# 1_-_MCU-CORE.net
KiCad netlist of a schematic drawn in Altium Designer
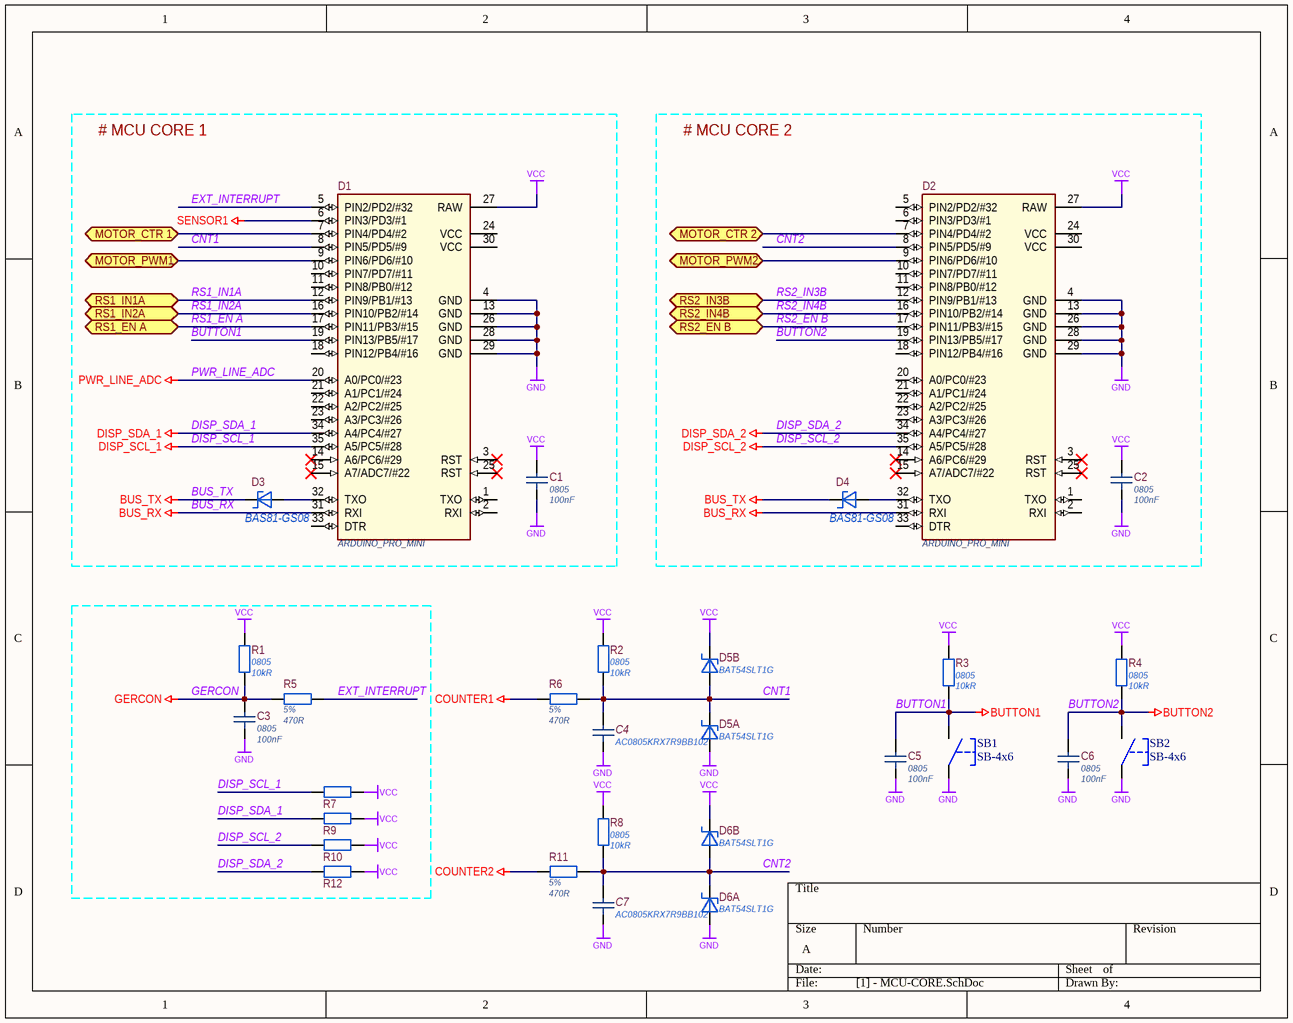
[diagram p0: [1] - MCU-CORE.SchDoc]

(export (version "E")
  (design (tool "Eeschema 10.0.6"))
  (components
    (comp (ref "C1")
      (value "AC0805KRX7R9BB104")
      (footprint "CH0805C")
      (description "0.10µF 50V Ceramic Capacitor X7R 0805 (2012 Metric) 0.079\" L x 0.049\" W (2.00mm x 1.25mm)")
      (fields
        (field (name "CASE/PACKAGE") "0805")
        (field (name "CAPACITANCE") "100nF")
        (field (name "TOLERANCE") "10%")
      )
      (libsource (lib "Chip Capacitors") (part "AC0805KRX7R9BB104"))
    )
    (comp (ref "C2")
      (value "AC0805KRX7R9BB104")
      (footprint "CH0805C")
      (description "0.10µF 50V Ceramic Capacitor X7R 0805 (2012 Metric) 0.079\" L x 0.049\" W (2.00mm x 1.25mm)")
      (fields
        (field (name "CASE/PACKAGE") "0805")
        (field (name "CAPACITANCE") "100nF")
        (field (name "TOLERANCE") "10%")
      )
      (libsource (lib "Chip Capacitors") (part "AC0805KRX7R9BB104"))
    )
    (comp (ref "C3")
      (value "AC0805KRX7R9BB104")
      (footprint "CH0805C")
      (description "0.10µF 50V Ceramic Capacitor X7R 0805 (2012 Metric) 0.079\" L x 0.049\" W (2.00mm x 1.25mm)")
      (fields
        (field (name "CASE/PACKAGE") "0805")
        (field (name "CAPACITANCE") "100nF")
        (field (name "TOLERANCE") "10%")
      )
      (libsource (lib "Chip Capacitors") (part "AC0805KRX7R9BB104"))
    )
    (comp (ref "C4")
      (value "AC0805KRX7R9BB102")
      (footprint "CH0805C")
      (description "CAP CER 1000PF 50V X7R 0805")
      (libsource (lib "Chip Capacitors") (part "AC0805KRX7R9BB102"))
    )
    (comp (ref "C5")
      (value "AC0805KRX7R9BB104")
      (footprint "CH0805C")
      (description "0.10µF 50V Ceramic Capacitor X7R 0805 (2012 Metric) 0.079\" L x 0.049\" W (2.00mm x 1.25mm)")
      (fields
        (field (name "CASE/PACKAGE") "0805")
        (field (name "CAPACITANCE") "100nF")
        (field (name "TOLERANCE") "10%")
      )
      (libsource (lib "Chip Capacitors") (part "AC0805KRX7R9BB104"))
    )
    (comp (ref "C6")
      (value "AC0805KRX7R9BB104")
      (footprint "CH0805C")
      (description "0.10µF 50V Ceramic Capacitor X7R 0805 (2012 Metric) 0.079\" L x 0.049\" W (2.00mm x 1.25mm)")
      (fields
        (field (name "CASE/PACKAGE") "0805")
        (field (name "CAPACITANCE") "100nF")
        (field (name "TOLERANCE") "10%")
      )
      (libsource (lib "Chip Capacitors") (part "AC0805KRX7R9BB104"))
    )
    (comp (ref "C7")
      (value "AC0805KRX7R9BB102")
      (footprint "CH0805C")
      (description "CAP CER 1000PF 50V X7R 0805")
      (libsource (lib "Chip Capacitors") (part "AC0805KRX7R9BB102"))
    )
    (comp (ref "D1")
      (value "ARDUINO_PRO_MINI")
      (footprint "DEV-11114")
      (description "ATMEGA328 ARDUINO PRO MINI 3.3V")
      (libsource (lib "Modules") (part "ARDUINO_PRO_MINI"))
    )
    (comp (ref "D2")
      (value "ARDUINO_PRO_MINI")
      (footprint "DEV-11114")
      (description "ATMEGA328 ARDUINO PRO MINI 3.3V")
      (libsource (lib "Modules") (part "ARDUINO_PRO_MINI"))
    )
    (comp (ref "D3")
      (value "BAS81-GS08")
      (footprint "SOD-80")
      (description "Diode Small Signal Schottky 40V 0.03A 2-Pin Mini-MELF SOD-80 T/R")
      (libsource (lib "Diodes") (part "BAS81-GS08"))
    )
    (comp (ref "D4")
      (value "BAS81-GS08")
      (footprint "SOD-80")
      (description "Diode Small Signal Schottky 40V 0.03A 2-Pin Mini-MELF SOD-80 T/R")
      (libsource (lib "Diodes") (part "BAS81-GS08"))
    )
    (comp (ref "D5")
      (value "BAT54SLT1G")
      (footprint "SOT23-3")
      (description "DIODE ARRAY SCHOTTKY 30V SOT23-3")
      (libsource (lib "Diodes") (part "BAT54SLT1G"))
    )
    (comp (ref "D6")
      (value "BAT54SLT1G")
      (footprint "SOT23-3")
      (description "DIODE ARRAY SCHOTTKY 30V SOT23-3")
      (libsource (lib "Diodes") (part "BAT54SLT1G"))
    )
    (comp (ref "R1")
      (value "RC0805JR-0710KL")
      (footprint "CH0805R")
      (description "RES SMD 10K OHM 5% 1/8W 0805")
      (fields
        (field (name "CASE/PACKAGE") "0805")
        (field (name "TOLERANCE") "5%")
        (field (name "RESISTANCE") "10kR")
      )
      (libsource (lib "Chip Resistors") (part "RC0805JR-0710KL"))
    )
    (comp (ref "R2")
      (value "RC0805JR-0710KL")
      (footprint "CH0805R")
      (description "RES SMD 10K OHM 5% 1/8W 0805")
      (fields
        (field (name "CASE/PACKAGE") "0805")
        (field (name "TOLERANCE") "5%")
        (field (name "RESISTANCE") "10kR")
      )
      (libsource (lib "Chip Resistors") (part "RC0805JR-0710KL"))
    )
    (comp (ref "R3")
      (value "RC0805JR-0710KL")
      (footprint "CH0805R")
      (description "RES SMD 10K OHM 5% 1/8W 0805")
      (fields
        (field (name "CASE/PACKAGE") "0805")
        (field (name "TOLERANCE") "5%")
        (field (name "RESISTANCE") "10kR")
      )
      (libsource (lib "Chip Resistors") (part "RC0805JR-0710KL"))
    )
    (comp (ref "R4")
      (value "RC0805JR-0710KL")
      (footprint "CH0805R")
      (description "RES SMD 10K OHM 5% 1/8W 0805")
      (fields
        (field (name "CASE/PACKAGE") "0805")
        (field (name "TOLERANCE") "5%")
        (field (name "RESISTANCE") "10kR")
      )
      (libsource (lib "Chip Resistors") (part "RC0805JR-0710KL"))
    )
    (comp (ref "R5")
      (value "RC0805JR-07470RL")
      (footprint "CH0805R")
      (description "RES SMD 470 OHM 5% 1/8W 0805")
      (fields (field (name "TOLERANCE") "5%") (field (name "RESISTANCE") "470R"))
      (libsource (lib "Chip Resistors") (part "RC0805JR-07470RL"))
    )
    (comp (ref "R6")
      (value "RC0805JR-07470RL")
      (footprint "CH0805R")
      (description "RES SMD 470 OHM 5% 1/8W 0805")
      (fields (field (name "TOLERANCE") "5%") (field (name "RESISTANCE") "470R"))
      (libsource (lib "Chip Resistors") (part "RC0805JR-07470RL"))
    )
    (comp (ref "R7")
      (value "RC0805JR-074K7L")
      (footprint "CH0805R")
      (description "RES SMD 4.7K OHM 5% 1/8W 0805")
      (fields (field (name "TOLERANCE") "5%"))
      (libsource (lib "Chip Resistors") (part "RC0805JR-074K7L"))
    )
    (comp (ref "R8")
      (value "RC0805JR-0710KL")
      (footprint "CH0805R")
      (description "RES SMD 10K OHM 5% 1/8W 0805")
      (fields
        (field (name "CASE/PACKAGE") "0805")
        (field (name "TOLERANCE") "5%")
        (field (name "RESISTANCE") "10kR")
      )
      (libsource (lib "Chip Resistors") (part "RC0805JR-0710KL"))
    )
    (comp (ref "R9")
      (value "RC0805JR-074K7L")
      (footprint "CH0805R")
      (description "RES SMD 4.7K OHM 5% 1/8W 0805")
      (fields (field (name "TOLERANCE") "5%"))
      (libsource (lib "Chip Resistors") (part "RC0805JR-074K7L"))
    )
    (comp (ref "R10")
      (value "RC0805JR-074K7L")
      (footprint "CH0805R")
      (description "RES SMD 4.7K OHM 5% 1/8W 0805")
      (fields (field (name "TOLERANCE") "5%"))
      (libsource (lib "Chip Resistors") (part "RC0805JR-074K7L"))
    )
    (comp (ref "R11")
      (value "RC0805JR-07470RL")
      (footprint "CH0805R")
      (description "RES SMD 470 OHM 5% 1/8W 0805")
      (fields (field (name "TOLERANCE") "5%") (field (name "RESISTANCE") "470R"))
      (libsource (lib "Chip Resistors") (part "RC0805JR-07470RL"))
    )
    (comp (ref "R12")
      (value "RC0805JR-074K7L")
      (footprint "CH0805R")
      (description "RES SMD 4.7K OHM 5% 1/8W 0805")
      (fields (field (name "TOLERANCE") "5%"))
      (libsource (lib "Chip Resistors") (part "RC0805JR-074K7L"))
    )
    (comp (ref "SB1")
      (value "SB-4x6")
      (footprint "Switch:Button-6*4.5")
      (libsource (lib "Switch") (part "SB-4x6"))
    )
    (comp (ref "SB2")
      (value "SB-4x6")
      (footprint "Switch:Button-6*4.5")
      (libsource (lib "Switch") (part "SB-4x6"))
    )
  )
  (nets
    (net (code "1") (name "/CNT1") (class "Default")
      (node (ref "C4") (pin "1") (pinfunction "1_1") (pintype "passive"))
      (node (ref "D1") (pin "8") (pinfunction "PIN5/PD5/#9_8") (pintype "bidirectional"))
      (node (ref "D5") (pin "3") (pintype "passive"))
      (node (ref "R2") (pin "1") (pinfunction "1_1") (pintype "passive"))
      (node (ref "R6") (pin "2") (pinfunction "2_2") (pintype "passive"))
    )
    (net (code "2") (name "/CNT2") (class "Default")
      (node (ref "C7") (pin "1") (pinfunction "1_1") (pintype "passive"))
      (node (ref "D2") (pin "8") (pinfunction "PIN5/PD5/#9_8") (pintype "bidirectional"))
      (node (ref "D6") (pin "3") (pintype "passive"))
      (node (ref "R11") (pin "2") (pinfunction "2_2") (pintype "passive"))
      (node (ref "R8") (pin "1") (pinfunction "1_1") (pintype "passive"))
    )
    (net (code "3") (name "/EXT_INTERRUPT") (class "Default")
      (node (ref "D1") (pin "5") (pinfunction "PIN2/PD2/#32_5") (pintype "bidirectional"))
      (node (ref "R5") (pin "2") (pinfunction "2_2") (pintype "passive"))
    )
    (net (code "4") (name "/MOTOR_CTR 1") (class "Default")
      (node (ref "D1") (pin "7") (pinfunction "PIN4/PD4/#2_7") (pintype "bidirectional"))
    )
    (net (code "5") (name "/MOTOR_CTR 2") (class "Default")
      (node (ref "D2") (pin "7") (pinfunction "PIN4/PD4/#2_7") (pintype "bidirectional"))
    )
    (net (code "6") (name "/MOTOR_PWM1") (class "Default")
      (node (ref "D1") (pin "9") (pinfunction "PIN6/PD6/#10_9") (pintype "bidirectional"))
    )
    (net (code "7") (name "/MOTOR_PWM2") (class "Default")
      (node (ref "D2") (pin "9") (pinfunction "PIN6/PD6/#10_9") (pintype "bidirectional"))
    )
    (net (code "8") (name "/RS1_EN A") (class "Default")
      (node (ref "D1") (pin "17") (pinfunction "PIN11/PB3/#15_17") (pintype "bidirectional"))
    )
    (net (code "9") (name "/RS1_IN1A") (class "Default")
      (node (ref "D1") (pin "12") (pinfunction "PIN9/PB1/#13_12") (pintype "bidirectional"))
    )
    (net (code "10") (name "/RS1_IN2A") (class "Default")
      (node (ref "D1") (pin "16") (pinfunction "PIN10/PB2/#14_16") (pintype "bidirectional"))
    )
    (net (code "11") (name "/RS2_EN B") (class "Default")
      (node (ref "D2") (pin "17") (pinfunction "PIN11/PB3/#15_17") (pintype "bidirectional"))
    )
    (net (code "12") (name "/RS2_IN3B") (class "Default")
      (node (ref "D2") (pin "12") (pinfunction "PIN9/PB1/#13_12") (pintype "bidirectional"))
    )
    (net (code "13") (name "/RS2_IN4B") (class "Default")
      (node (ref "D2") (pin "16") (pinfunction "PIN10/PB2/#14_16") (pintype "bidirectional"))
    )
    (net (code "14") (name "BUS_RX") (class "Default")
      (node (ref "D1") (pin "31") (pinfunction "RXI_31") (pintype "bidirectional"))
      (node (ref "D2") (pin "31") (pinfunction "RXI_31") (pintype "bidirectional"))
    )
    (net (code "15") (name "BUS_TX") (class "Default")
      (node (ref "D3") (pin "2") (pinfunction "K_2") (pintype "passive"))
      (node (ref "D4") (pin "2") (pinfunction "K_2") (pintype "passive"))
    )
    (net (code "16") (name "BUTTON1") (class "Default")
      (node (ref "C5") (pin "1") (pinfunction "1_1") (pintype "passive"))
      (node (ref "D1") (pin "19") (pinfunction "PIN13/PB5/#17_19") (pintype "bidirectional"))
      (node (ref "R3") (pin "1") (pinfunction "1_1") (pintype "passive"))
      (node (ref "SB1") (pin "2") (pinfunction "2_2") (pintype "passive"))
    )
    (net (code "17") (name "BUTTON2") (class "Default")
      (node (ref "C6") (pin "1") (pinfunction "1_1") (pintype "passive"))
      (node (ref "D2") (pin "19") (pinfunction "PIN13/PB5/#17_19") (pintype "bidirectional"))
      (node (ref "R4") (pin "1") (pinfunction "1_1") (pintype "passive"))
      (node (ref "SB2") (pin "2") (pinfunction "2_2") (pintype "passive"))
    )
    (net (code "18") (name "COUNTER1") (class "Default")
      (node (ref "R6") (pin "1") (pinfunction "1_1") (pintype "passive"))
    )
    (net (code "19") (name "COUNTER2") (class "Default")
      (node (ref "R11") (pin "1") (pinfunction "1_1") (pintype "passive"))
    )
    (net (code "20") (name "DISP_SCL_1") (class "Default")
      (node (ref "D1") (pin "35") (pinfunction "A5/PC5/#28_35") (pintype "bidirectional"))
      (node (ref "R7") (pin "2") (pinfunction "2_2") (pintype "passive"))
    )
    (net (code "21") (name "DISP_SCL_2") (class "Default")
      (node (ref "D2") (pin "35") (pinfunction "A5/PC5/#28_35") (pintype "bidirectional"))
      (node (ref "R10") (pin "2") (pinfunction "2_2") (pintype "passive"))
    )
    (net (code "22") (name "DISP_SDA_1") (class "Default")
      (node (ref "D1") (pin "34") (pinfunction "A4/PC4/#27_34") (pintype "bidirectional"))
      (node (ref "R9") (pin "2") (pinfunction "2_2") (pintype "passive"))
    )
    (net (code "23") (name "DISP_SDA_2") (class "Default")
      (node (ref "D2") (pin "34") (pinfunction "A4/PC4/#27_34") (pintype "bidirectional"))
      (node (ref "R12") (pin "2") (pinfunction "2_2") (pintype "passive"))
    )
    (net (code "24") (name "GERCON") (class "Default")
      (node (ref "C3") (pin "1") (pinfunction "1_1") (pintype "passive"))
      (node (ref "R1") (pin "1") (pinfunction "1_1") (pintype "passive"))
      (node (ref "R5") (pin "1") (pinfunction "1_1") (pintype "passive"))
    )
    (net (code "25") (name "GND") (class "Default")
      (node (ref "C1") (pin "2") (pinfunction "2_2") (pintype "passive"))
      (node (ref "C2") (pin "2") (pinfunction "2_2") (pintype "passive"))
      (node (ref "C3") (pin "2") (pinfunction "2_2") (pintype "passive"))
      (node (ref "C4") (pin "2") (pinfunction "2_2") (pintype "passive"))
      (node (ref "C5") (pin "2") (pinfunction "2_2") (pintype "passive"))
      (node (ref "C6") (pin "2") (pinfunction "2_2") (pintype "passive"))
      (node (ref "C7") (pin "2") (pinfunction "2_2") (pintype "passive"))
      (node (ref "D1") (pin "13") (pinfunction "GND_13") (pintype "power_in"))
      (node (ref "D1") (pin "26") (pinfunction "GND_26") (pintype "power_in"))
      (node (ref "D1") (pin "28") (pinfunction "GND_28") (pintype "power_in"))
      (node (ref "D1") (pin "29") (pinfunction "GND_29") (pintype "power_in"))
      (node (ref "D1") (pin "4") (pinfunction "GND_4") (pintype "power_in"))
      (node (ref "D2") (pin "13") (pinfunction "GND_13") (pintype "power_in"))
      (node (ref "D2") (pin "26") (pinfunction "GND_26") (pintype "power_in"))
      (node (ref "D2") (pin "28") (pinfunction "GND_28") (pintype "power_in"))
      (node (ref "D2") (pin "29") (pinfunction "GND_29") (pintype "power_in"))
      (node (ref "D2") (pin "4") (pinfunction "GND_4") (pintype "power_in"))
      (node (ref "D5") (pin "1") (pintype "passive"))
      (node (ref "D6") (pin "1") (pintype "passive"))
      (node (ref "SB1") (pin "1") (pinfunction "1_1") (pintype "passive"))
      (node (ref "SB2") (pin "1") (pinfunction "1_1") (pintype "passive"))
    )
    (net (code "26") (name "Net-(D3-A)") (class "Default")
      (node (ref "D1") (pin "32") (pinfunction "TXO_32") (pintype "bidirectional"))
      (node (ref "D3") (pin "1") (pinfunction "A_1") (pintype "passive"))
    )
    (net (code "27") (name "Net-(D4-A)") (class "Default")
      (node (ref "D2") (pin "32") (pinfunction "TXO_32") (pintype "bidirectional"))
      (node (ref "D4") (pin "1") (pinfunction "A_1") (pintype "passive"))
    )
    (net (code "28") (name "PWR_LINE_ADC") (class "Default")
      (node (ref "D1") (pin "20") (pinfunction "A0/PC0/#23_20") (pintype "bidirectional"))
    )
    (net (code "29") (name "SENSOR1") (class "Default")
      (node (ref "D1") (pin "6") (pinfunction "PIN3/PD3/#1_6") (pintype "bidirectional"))
    )
    (net (code "30") (name "VCC") (class "Default")
      (node (ref "C1") (pin "1") (pinfunction "1_1") (pintype "passive"))
      (node (ref "C2") (pin "1") (pinfunction "1_1") (pintype "passive"))
      (node (ref "D1") (pin "27") (pinfunction "RAW_27") (pintype "power_in"))
      (node (ref "D2") (pin "27") (pinfunction "RAW_27") (pintype "power_in"))
      (node (ref "D5") (pin "2") (pintype "passive"))
      (node (ref "D6") (pin "2") (pintype "passive"))
      (node (ref "R1") (pin "2") (pinfunction "2_2") (pintype "passive"))
      (node (ref "R10") (pin "1") (pinfunction "1_1") (pintype "passive"))
      (node (ref "R12") (pin "1") (pinfunction "1_1") (pintype "passive"))
      (node (ref "R2") (pin "2") (pinfunction "2_2") (pintype "passive"))
      (node (ref "R3") (pin "2") (pinfunction "2_2") (pintype "passive"))
      (node (ref "R4") (pin "2") (pinfunction "2_2") (pintype "passive"))
      (node (ref "R7") (pin "1") (pinfunction "1_1") (pintype "passive"))
      (node (ref "R8") (pin "2") (pinfunction "2_2") (pintype "passive"))
      (node (ref "R9") (pin "1") (pinfunction "1_1") (pintype "passive"))
    )
    (net (code "31") (name "unconnected-(D1-A1{slash}PC1{slash}#24-Pad21)") (class "Default")
      (node (ref "D1") (pin "21") (pinfunction "A1/PC1/#24_21") (pintype "bidirectional"))
    )
    (net (code "32") (name "unconnected-(D1-A2{slash}PC2{slash}#25-Pad22)") (class "Default")
      (node (ref "D1") (pin "22") (pinfunction "A2/PC2/#25_22") (pintype "bidirectional"))
    )
    (net (code "33") (name "unconnected-(D1-A3{slash}PC3{slash}#26-Pad23)") (class "Default")
      (node (ref "D1") (pin "23") (pinfunction "A3/PC3/#26_23") (pintype "bidirectional"))
    )
    (net (code "34") (name "unconnected-(D1-A6{slash}PC6{slash}#29-Pad14)") (class "Default")
      (node (ref "D1") (pin "14") (pinfunction "A6/PC6/#29_14") (pintype "input+no_connect"))
    )
    (net (code "35") (name "unconnected-(D1-A7{slash}ADC7{slash}#22-Pad15)") (class "Default")
      (node (ref "D1") (pin "15") (pinfunction "A7/ADC7/#22_15") (pintype "input+no_connect"))
    )
    (net (code "36") (name "unconnected-(D1-DTR-Pad33)") (class "Default")
      (node (ref "D1") (pin "33") (pinfunction "DTR_33") (pintype "bidirectional"))
    )
    (net (code "37") (name "unconnected-(D1-PIN7{slash}PD7{slash}#11-Pad10)") (class "Default")
      (node (ref "D1") (pin "10") (pinfunction "PIN7/PD7/#11_10") (pintype "bidirectional"))
    )
    (net (code "38") (name "unconnected-(D1-PIN8{slash}PB0{slash}#12-Pad11)") (class "Default")
      (node (ref "D1") (pin "11") (pinfunction "PIN8/PB0/#12_11") (pintype "bidirectional"))
    )
    (net (code "39") (name "unconnected-(D1-PIN12{slash}PB4{slash}#16-Pad18)") (class "Default")
      (node (ref "D1") (pin "18") (pinfunction "PIN12/PB4/#16_18") (pintype "bidirectional"))
    )
    (net (code "40") (name "unconnected-(D1-RST-Pad3)") (class "Default")
      (node (ref "D1") (pin "3") (pinfunction "RST_3") (pintype "input+no_connect"))
    )
    (net (code "41") (name "unconnected-(D1-RST-Pad25)") (class "Default")
      (node (ref "D1") (pin "25") (pinfunction "RST_25") (pintype "input+no_connect"))
    )
    (net (code "42") (name "unconnected-(D1-RXI-Pad2)") (class "Default")
      (node (ref "D1") (pin "2") (pinfunction "RXI_2") (pintype "bidirectional"))
    )
    (net (code "43") (name "unconnected-(D1-TXO-Pad1)") (class "Default")
      (node (ref "D1") (pin "1") (pinfunction "TXO_1") (pintype "bidirectional"))
    )
    (net (code "44") (name "unconnected-(D1-VCC-Pad24)") (class "Default")
      (node (ref "D1") (pin "24") (pinfunction "VCC_24") (pintype "power_in"))
    )
    (net (code "45") (name "unconnected-(D1-VCC-Pad30)") (class "Default")
      (node (ref "D1") (pin "30") (pinfunction "VCC_30") (pintype "power_in"))
    )
    (net (code "46") (name "unconnected-(D2-A0{slash}PC0{slash}#23-Pad20)") (class "Default")
      (node (ref "D2") (pin "20") (pinfunction "A0/PC0/#23_20") (pintype "bidirectional"))
    )
    (net (code "47") (name "unconnected-(D2-A1{slash}PC1{slash}#24-Pad21)") (class "Default")
      (node (ref "D2") (pin "21") (pinfunction "A1/PC1/#24_21") (pintype "bidirectional"))
    )
    (net (code "48") (name "unconnected-(D2-A2{slash}PC2{slash}#25-Pad22)") (class "Default")
      (node (ref "D2") (pin "22") (pinfunction "A2/PC2/#25_22") (pintype "bidirectional"))
    )
    (net (code "49") (name "unconnected-(D2-A3{slash}PC3{slash}#26-Pad23)") (class "Default")
      (node (ref "D2") (pin "23") (pinfunction "A3/PC3/#26_23") (pintype "bidirectional"))
    )
    (net (code "50") (name "unconnected-(D2-A6{slash}PC6{slash}#29-Pad14)") (class "Default")
      (node (ref "D2") (pin "14") (pinfunction "A6/PC6/#29_14") (pintype "input+no_connect"))
    )
    (net (code "51") (name "unconnected-(D2-A7{slash}ADC7{slash}#22-Pad15)") (class "Default")
      (node (ref "D2") (pin "15") (pinfunction "A7/ADC7/#22_15") (pintype "input+no_connect"))
    )
    (net (code "52") (name "unconnected-(D2-DTR-Pad33)") (class "Default")
      (node (ref "D2") (pin "33") (pinfunction "DTR_33") (pintype "bidirectional"))
    )
    (net (code "53") (name "unconnected-(D2-PIN2{slash}PD2{slash}#32-Pad5)") (class "Default")
      (node (ref "D2") (pin "5") (pinfunction "PIN2/PD2/#32_5") (pintype "bidirectional"))
    )
    (net (code "54") (name "unconnected-(D2-PIN3{slash}PD3{slash}#1-Pad6)") (class "Default")
      (node (ref "D2") (pin "6") (pinfunction "PIN3/PD3/#1_6") (pintype "bidirectional"))
    )
    (net (code "55") (name "unconnected-(D2-PIN7{slash}PD7{slash}#11-Pad10)") (class "Default")
      (node (ref "D2") (pin "10") (pinfunction "PIN7/PD7/#11_10") (pintype "bidirectional"))
    )
    (net (code "56") (name "unconnected-(D2-PIN8{slash}PB0{slash}#12-Pad11)") (class "Default")
      (node (ref "D2") (pin "11") (pinfunction "PIN8/PB0/#12_11") (pintype "bidirectional"))
    )
    (net (code "57") (name "unconnected-(D2-PIN12{slash}PB4{slash}#16-Pad18)") (class "Default")
      (node (ref "D2") (pin "18") (pinfunction "PIN12/PB4/#16_18") (pintype "bidirectional"))
    )
    (net (code "58") (name "unconnected-(D2-RST-Pad3)") (class "Default")
      (node (ref "D2") (pin "3") (pinfunction "RST_3") (pintype "input+no_connect"))
    )
    (net (code "59") (name "unconnected-(D2-RST-Pad25)") (class "Default")
      (node (ref "D2") (pin "25") (pinfunction "RST_25") (pintype "input+no_connect"))
    )
    (net (code "60") (name "unconnected-(D2-RXI-Pad2)") (class "Default")
      (node (ref "D2") (pin "2") (pinfunction "RXI_2") (pintype "bidirectional"))
    )
    (net (code "61") (name "unconnected-(D2-TXO-Pad1)") (class "Default")
      (node (ref "D2") (pin "1") (pinfunction "TXO_1") (pintype "bidirectional"))
    )
    (net (code "62") (name "unconnected-(D2-VCC-Pad24)") (class "Default")
      (node (ref "D2") (pin "24") (pinfunction "VCC_24") (pintype "power_in"))
    )
    (net (code "63") (name "unconnected-(D2-VCC-Pad30)") (class "Default")
      (node (ref "D2") (pin "30") (pinfunction "VCC_30") (pintype "power_in"))
    )
  )
)
